# Sheet1.net
KiCad netlist of a schematic drawn in Altium Designer
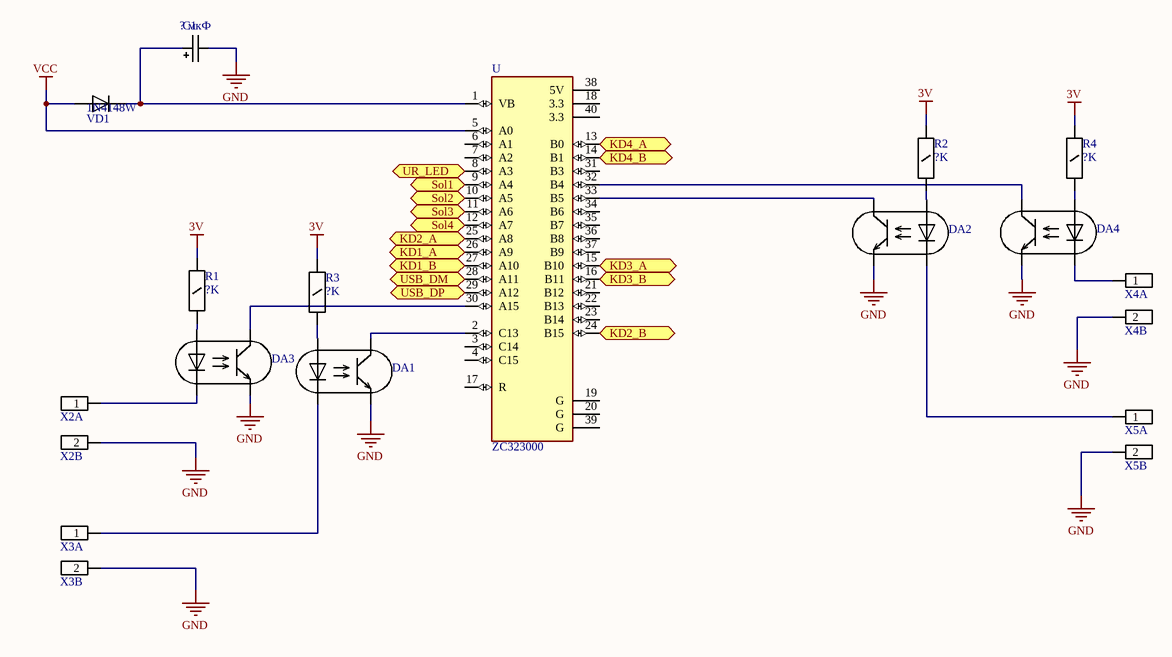
[diagram p0: Sheet1.SchDoc]

(export (version "E")
  (design (tool "Eeschema 10.0.6"))
  (components
    (comp (ref "C1")
      (value "? мкФ")
      (footprint "C_16x7.5")
      (description "К50-35")
      (fields (field (name "TOLERANCE") "20%"))
      (libsource (lib "Res_end_Cap") (part "Конденсатор 16х7.5"))
    )
    (comp (ref "DA1")
      (value "KPC357NT")
      (footprint "Mini-flat-4")
      (description "оптрон, SMD")
      (libsource (lib "") (part "KPC357NT_1"))
    )
    (comp (ref "DA2")
      (value "KPC357NT")
      (footprint "Mini-flat-4")
      (description "оптрон, SMD")
      (libsource (lib "LEDendIND") (part "KPC357NT"))
    )
    (comp (ref "DA3")
      (value "KPC357NT")
      (footprint "Mini-flat-4")
      (description "оптрон, SMD")
      (libsource (lib "") (part "KPC357NT_1"))
    )
    (comp (ref "DA4")
      (value "KPC357NT")
      (footprint "Mini-flat-4")
      (description "оптрон, SMD")
      (libsource (lib "LEDendIND") (part "KPC357NT"))
    )
    (comp (ref "R1")
      (value "?K")
      (footprint "R_1206")
      (description "0,25 Вт")
      (fields (field (name "POWER") "0.25 Вт") (field (name "TOLERANCE") "5%"))
      (libsource (lib "Res_end_Cap") (part "Резистор 1206"))
    )
    (comp (ref "R2")
      (value "?K")
      (footprint "R_1206")
      (description "0,25 Вт")
      (fields (field (name "POWER") "0.25 Вт") (field (name "TOLERANCE") "5%"))
      (libsource (lib "Res_end_Cap") (part "Резистор 1206"))
    )
    (comp (ref "R3")
      (value "?K")
      (footprint "R_1206")
      (description "0,25 Вт")
      (fields (field (name "POWER") "0.25 Вт") (field (name "TOLERANCE") "5%"))
      (libsource (lib "Res_end_Cap") (part "Резистор 1206"))
    )
    (comp (ref "R4")
      (value "?K")
      (footprint "R_1206")
      (description "0,25 Вт")
      (fields (field (name "POWER") "0.25 Вт") (field (name "TOLERANCE") "5%"))
      (libsource (lib "Res_end_Cap") (part "Резистор 1206"))
    )
    (comp (ref "U")
      (value "ZC323000")
      (footprint "MODULE_ZC323000:MODULE_ZC323000")
      (description "STM32F103C8T6 ARM STM32 Minimum System Development Board Module For Arduino")
      (fields (field (name "MF") "YKS"))
      (libsource (lib "ZC323000") (part "ZC323000"))
    )
    (comp (ref "VD1")
      (value "1N4148W")
      (footprint "SOD-123")
      (description "диод, SMD")
      (fields (field (name "POWER") "410 мВт"))
      (libsource (lib "Диоды и транзисторы") (part "1N4148W"))
    )
    (comp (ref "X2")
      (value "DG508V-02")
      (footprint "DG508V-02")
      (description "клеммник винтовой 2к.,5.08мм")
      (libsource (lib "Klemniki") (part "DG508V-02"))
    )
    (comp (ref "X3")
      (value "DG508V-02")
      (footprint "DG508V-02")
      (description "клеммник винтовой 2к.,5.08мм")
      (libsource (lib "Klemniki") (part "DG508V-02"))
    )
    (comp (ref "X4")
      (value "DG508V-02")
      (footprint "DG508V-02")
      (description "клеммник винтовой 2к.,5.08мм")
      (libsource (lib "Klemniki") (part "DG508V-02"))
    )
    (comp (ref "X5")
      (value "DG508V-02")
      (footprint "DG508V-02")
      (description "клеммник винтовой 2к.,5.08мм")
      (libsource (lib "Klemniki") (part "DG508V-02"))
    )
  )
  (nets
    (net (code "1") (name "/KD1_A") (class "Default")
      (node (ref "U") (pin "26") (pinfunction "A9_26") (pintype "bidirectional"))
    )
    (net (code "2") (name "/KD1_B") (class "Default")
      (node (ref "U") (pin "27") (pinfunction "A10_27") (pintype "bidirectional"))
    )
    (net (code "3") (name "/KD2_A") (class "Default")
      (node (ref "U") (pin "25") (pinfunction "A8_25") (pintype "bidirectional"))
    )
    (net (code "4") (name "/KD2_B") (class "Default")
      (node (ref "U") (pin "24") (pinfunction "B15_24") (pintype "bidirectional"))
    )
    (net (code "5") (name "/KD3_A") (class "Default")
      (node (ref "U") (pin "15") (pinfunction "B10_15") (pintype "bidirectional"))
    )
    (net (code "6") (name "/KD3_B") (class "Default")
      (node (ref "U") (pin "16") (pinfunction "B11_16") (pintype "bidirectional"))
    )
    (net (code "7") (name "/KD4_A") (class "Default")
      (node (ref "U") (pin "13") (pinfunction "B0_13") (pintype "bidirectional"))
    )
    (net (code "8") (name "/KD4_B") (class "Default")
      (node (ref "U") (pin "14") (pinfunction "B1_14") (pintype "bidirectional"))
    )
    (net (code "9") (name "/Sol1") (class "Default")
      (node (ref "U") (pin "9") (pinfunction "A4_9") (pintype "bidirectional"))
    )
    (net (code "10") (name "/Sol2") (class "Default")
      (node (ref "U") (pin "10") (pinfunction "A5_10") (pintype "bidirectional"))
    )
    (net (code "11") (name "/Sol3") (class "Default")
      (node (ref "U") (pin "11") (pinfunction "A6_11") (pintype "bidirectional"))
    )
    (net (code "12") (name "/Sol4") (class "Default")
      (node (ref "U") (pin "12") (pinfunction "A7_12") (pintype "bidirectional"))
    )
    (net (code "13") (name "/UR_LED") (class "Default")
      (node (ref "U") (pin "8") (pinfunction "A3_8") (pintype "bidirectional"))
    )
    (net (code "14") (name "/USB_DM") (class "Default")
      (node (ref "U") (pin "28") (pinfunction "A11_28") (pintype "bidirectional"))
    )
    (net (code "15") (name "/USB_DP") (class "Default")
      (node (ref "U") (pin "29") (pinfunction "A12_29") (pintype "bidirectional"))
    )
    (net (code "16") (name "3V") (class "Default")
      (node (ref "R1") (pin "1") (pinfunction "1_1") (pintype "passive"))
      (node (ref "R2") (pin "1") (pinfunction "1_1") (pintype "passive"))
      (node (ref "R3") (pin "1") (pinfunction "1_1") (pintype "passive"))
      (node (ref "R4") (pin "1") (pinfunction "1_1") (pintype "passive"))
    )
    (net (code "17") (name "GND") (class "Default")
      (node (ref "C1") (pin "2") (pinfunction "2_2") (pintype "passive"))
      (node (ref "DA1") (pin "3") (pinfunction "3_3") (pintype "passive"))
      (node (ref "DA2") (pin "3") (pinfunction "3_3") (pintype "passive"))
      (node (ref "DA3") (pin "3") (pinfunction "3_3") (pintype "passive"))
      (node (ref "DA4") (pin "3") (pinfunction "3_3") (pintype "passive"))
      (node (ref "X2") (pin "2") (pinfunction "2_2") (pintype "passive"))
      (node (ref "X3") (pin "2") (pinfunction "2_2") (pintype "passive"))
      (node (ref "X4") (pin "2") (pinfunction "2_2") (pintype "passive"))
      (node (ref "X5") (pin "2") (pinfunction "2_2") (pintype "passive"))
    )
    (net (code "18") (name "Net-(DA1-Pad1)") (class "Default")
      (node (ref "DA1") (pin "1") (pinfunction "1_1") (pintype "passive"))
      (node (ref "R3") (pin "2") (pinfunction "2_2") (pintype "passive"))
    )
    (net (code "19") (name "Net-(DA1-Pad2)") (class "Default")
      (node (ref "DA1") (pin "2") (pinfunction "2_2") (pintype "passive"))
      (node (ref "X3") (pin "1") (pinfunction "1_1") (pintype "passive"))
    )
    (net (code "20") (name "Net-(DA2-Pad1)") (class "Default")
      (node (ref "DA2") (pin "1") (pinfunction "1_1") (pintype "passive"))
      (node (ref "R2") (pin "2") (pinfunction "2_2") (pintype "passive"))
    )
    (net (code "21") (name "Net-(DA2-Pad2)") (class "Default")
      (node (ref "DA2") (pin "2") (pinfunction "2_2") (pintype "passive"))
      (node (ref "X5") (pin "1") (pinfunction "1_1") (pintype "passive"))
    )
    (net (code "22") (name "Net-(DA3-Pad1)") (class "Default")
      (node (ref "DA3") (pin "1") (pinfunction "1_1") (pintype "passive"))
      (node (ref "R1") (pin "2") (pinfunction "2_2") (pintype "passive"))
    )
    (net (code "23") (name "Net-(DA3-Pad2)") (class "Default")
      (node (ref "DA3") (pin "2") (pinfunction "2_2") (pintype "passive"))
      (node (ref "X2") (pin "1") (pinfunction "1_1") (pintype "passive"))
    )
    (net (code "24") (name "Net-(DA4-Pad1)") (class "Default")
      (node (ref "DA4") (pin "1") (pinfunction "1_1") (pintype "passive"))
      (node (ref "R4") (pin "2") (pinfunction "2_2") (pintype "passive"))
    )
    (net (code "25") (name "Net-(DA4-Pad2)") (class "Default")
      (node (ref "DA4") (pin "2") (pinfunction "2_2") (pintype "passive"))
      (node (ref "X4") (pin "1") (pinfunction "1_1") (pintype "passive"))
    )
    (net (code "26") (name "Net-(U-A15)") (class "Default")
      (node (ref "DA3") (pin "4") (pinfunction "4_4") (pintype "passive"))
      (node (ref "U") (pin "30") (pinfunction "A15_30") (pintype "bidirectional"))
    )
    (net (code "27") (name "Net-(U-B4)") (class "Default")
      (node (ref "DA4") (pin "4") (pinfunction "4_4") (pintype "passive"))
      (node (ref "U") (pin "32") (pinfunction "B4_32") (pintype "bidirectional"))
    )
    (net (code "28") (name "Net-(U-B5)") (class "Default")
      (node (ref "DA2") (pin "4") (pinfunction "4_4") (pintype "passive"))
      (node (ref "U") (pin "33") (pinfunction "B5_33") (pintype "bidirectional"))
    )
    (net (code "29") (name "Net-(U-C13)") (class "Default")
      (node (ref "DA1") (pin "4") (pinfunction "4_4") (pintype "passive"))
      (node (ref "U") (pin "2") (pinfunction "C13_2") (pintype "bidirectional"))
    )
    (net (code "30") (name "Net-(U-VB)") (class "Default")
      (node (ref "C1") (pin "1") (pinfunction "1_1") (pintype "passive"))
      (node (ref "U") (pin "1") (pinfunction "VB_1") (pintype "bidirectional"))
      (node (ref "VD1") (pin "K") (pinfunction "K_K") (pintype "passive"))
    )
    (net (code "31") (name "VCC") (class "Default")
      (node (ref "U") (pin "5") (pinfunction "A0_5") (pintype "bidirectional"))
      (node (ref "VD1") (pin "A") (pinfunction "A_A") (pintype "passive"))
    )
    (net (code "32") (name "unconnected-(U-3.3-Pad18)") (class "Default")
      (node (ref "U") (pin "18") (pinfunction "3.3_18") (pintype "power_in"))
    )
    (net (code "33") (name "unconnected-(U-3.3-Pad40)") (class "Default")
      (node (ref "U") (pin "40") (pinfunction "3.3_40") (pintype "power_in"))
    )
    (net (code "34") (name "unconnected-(U-5V-Pad38)") (class "Default")
      (node (ref "U") (pin "38") (pinfunction "5V_38") (pintype "power_in"))
    )
    (net (code "35") (name "unconnected-(U-A1-Pad6)") (class "Default")
      (node (ref "U") (pin "6") (pinfunction "A1_6") (pintype "bidirectional"))
    )
    (net (code "36") (name "unconnected-(U-A2-Pad7)") (class "Default")
      (node (ref "U") (pin "7") (pinfunction "A2_7") (pintype "bidirectional"))
    )
    (net (code "37") (name "unconnected-(U-B3-Pad31)") (class "Default")
      (node (ref "U") (pin "31") (pinfunction "B3_31") (pintype "bidirectional"))
    )
    (net (code "38") (name "unconnected-(U-B6-Pad34)") (class "Default")
      (node (ref "U") (pin "34") (pinfunction "B6_34") (pintype "bidirectional"))
    )
    (net (code "39") (name "unconnected-(U-B7-Pad35)") (class "Default")
      (node (ref "U") (pin "35") (pinfunction "B7_35") (pintype "bidirectional"))
    )
    (net (code "40") (name "unconnected-(U-B8-Pad36)") (class "Default")
      (node (ref "U") (pin "36") (pinfunction "B8_36") (pintype "bidirectional"))
    )
    (net (code "41") (name "unconnected-(U-B9-Pad37)") (class "Default")
      (node (ref "U") (pin "37") (pinfunction "B9_37") (pintype "bidirectional"))
    )
    (net (code "42") (name "unconnected-(U-B12-Pad21)") (class "Default")
      (node (ref "U") (pin "21") (pinfunction "B12_21") (pintype "bidirectional"))
    )
    (net (code "43") (name "unconnected-(U-B13-Pad22)") (class "Default")
      (node (ref "U") (pin "22") (pinfunction "B13_22") (pintype "bidirectional"))
    )
    (net (code "44") (name "unconnected-(U-B14-Pad23)") (class "Default")
      (node (ref "U") (pin "23") (pinfunction "B14_23") (pintype "bidirectional"))
    )
    (net (code "45") (name "unconnected-(U-C14-Pad3)") (class "Default")
      (node (ref "U") (pin "3") (pinfunction "C14_3") (pintype "bidirectional"))
    )
    (net (code "46") (name "unconnected-(U-C15-Pad4)") (class "Default")
      (node (ref "U") (pin "4") (pinfunction "C15_4") (pintype "bidirectional"))
    )
    (net (code "47") (name "unconnected-(U-G-Pad19)") (class "Default")
      (node (ref "U") (pin "19") (pinfunction "G_19") (pintype "power_in"))
    )
    (net (code "48") (name "unconnected-(U-G-Pad20)") (class "Default")
      (node (ref "U") (pin "20") (pinfunction "G_20") (pintype "power_in"))
    )
    (net (code "49") (name "unconnected-(U-G-Pad39)") (class "Default")
      (node (ref "U") (pin "39") (pinfunction "G_39") (pintype "power_in"))
    )
    (net (code "50") (name "unconnected-(U-R-Pad17)") (class "Default")
      (node (ref "U") (pin "17") (pinfunction "R_17") (pintype "bidirectional"))
    )
  )
)
